# 03_Inputs_10-18.net
KiCad netlist of a schematic drawn in Altium Designer
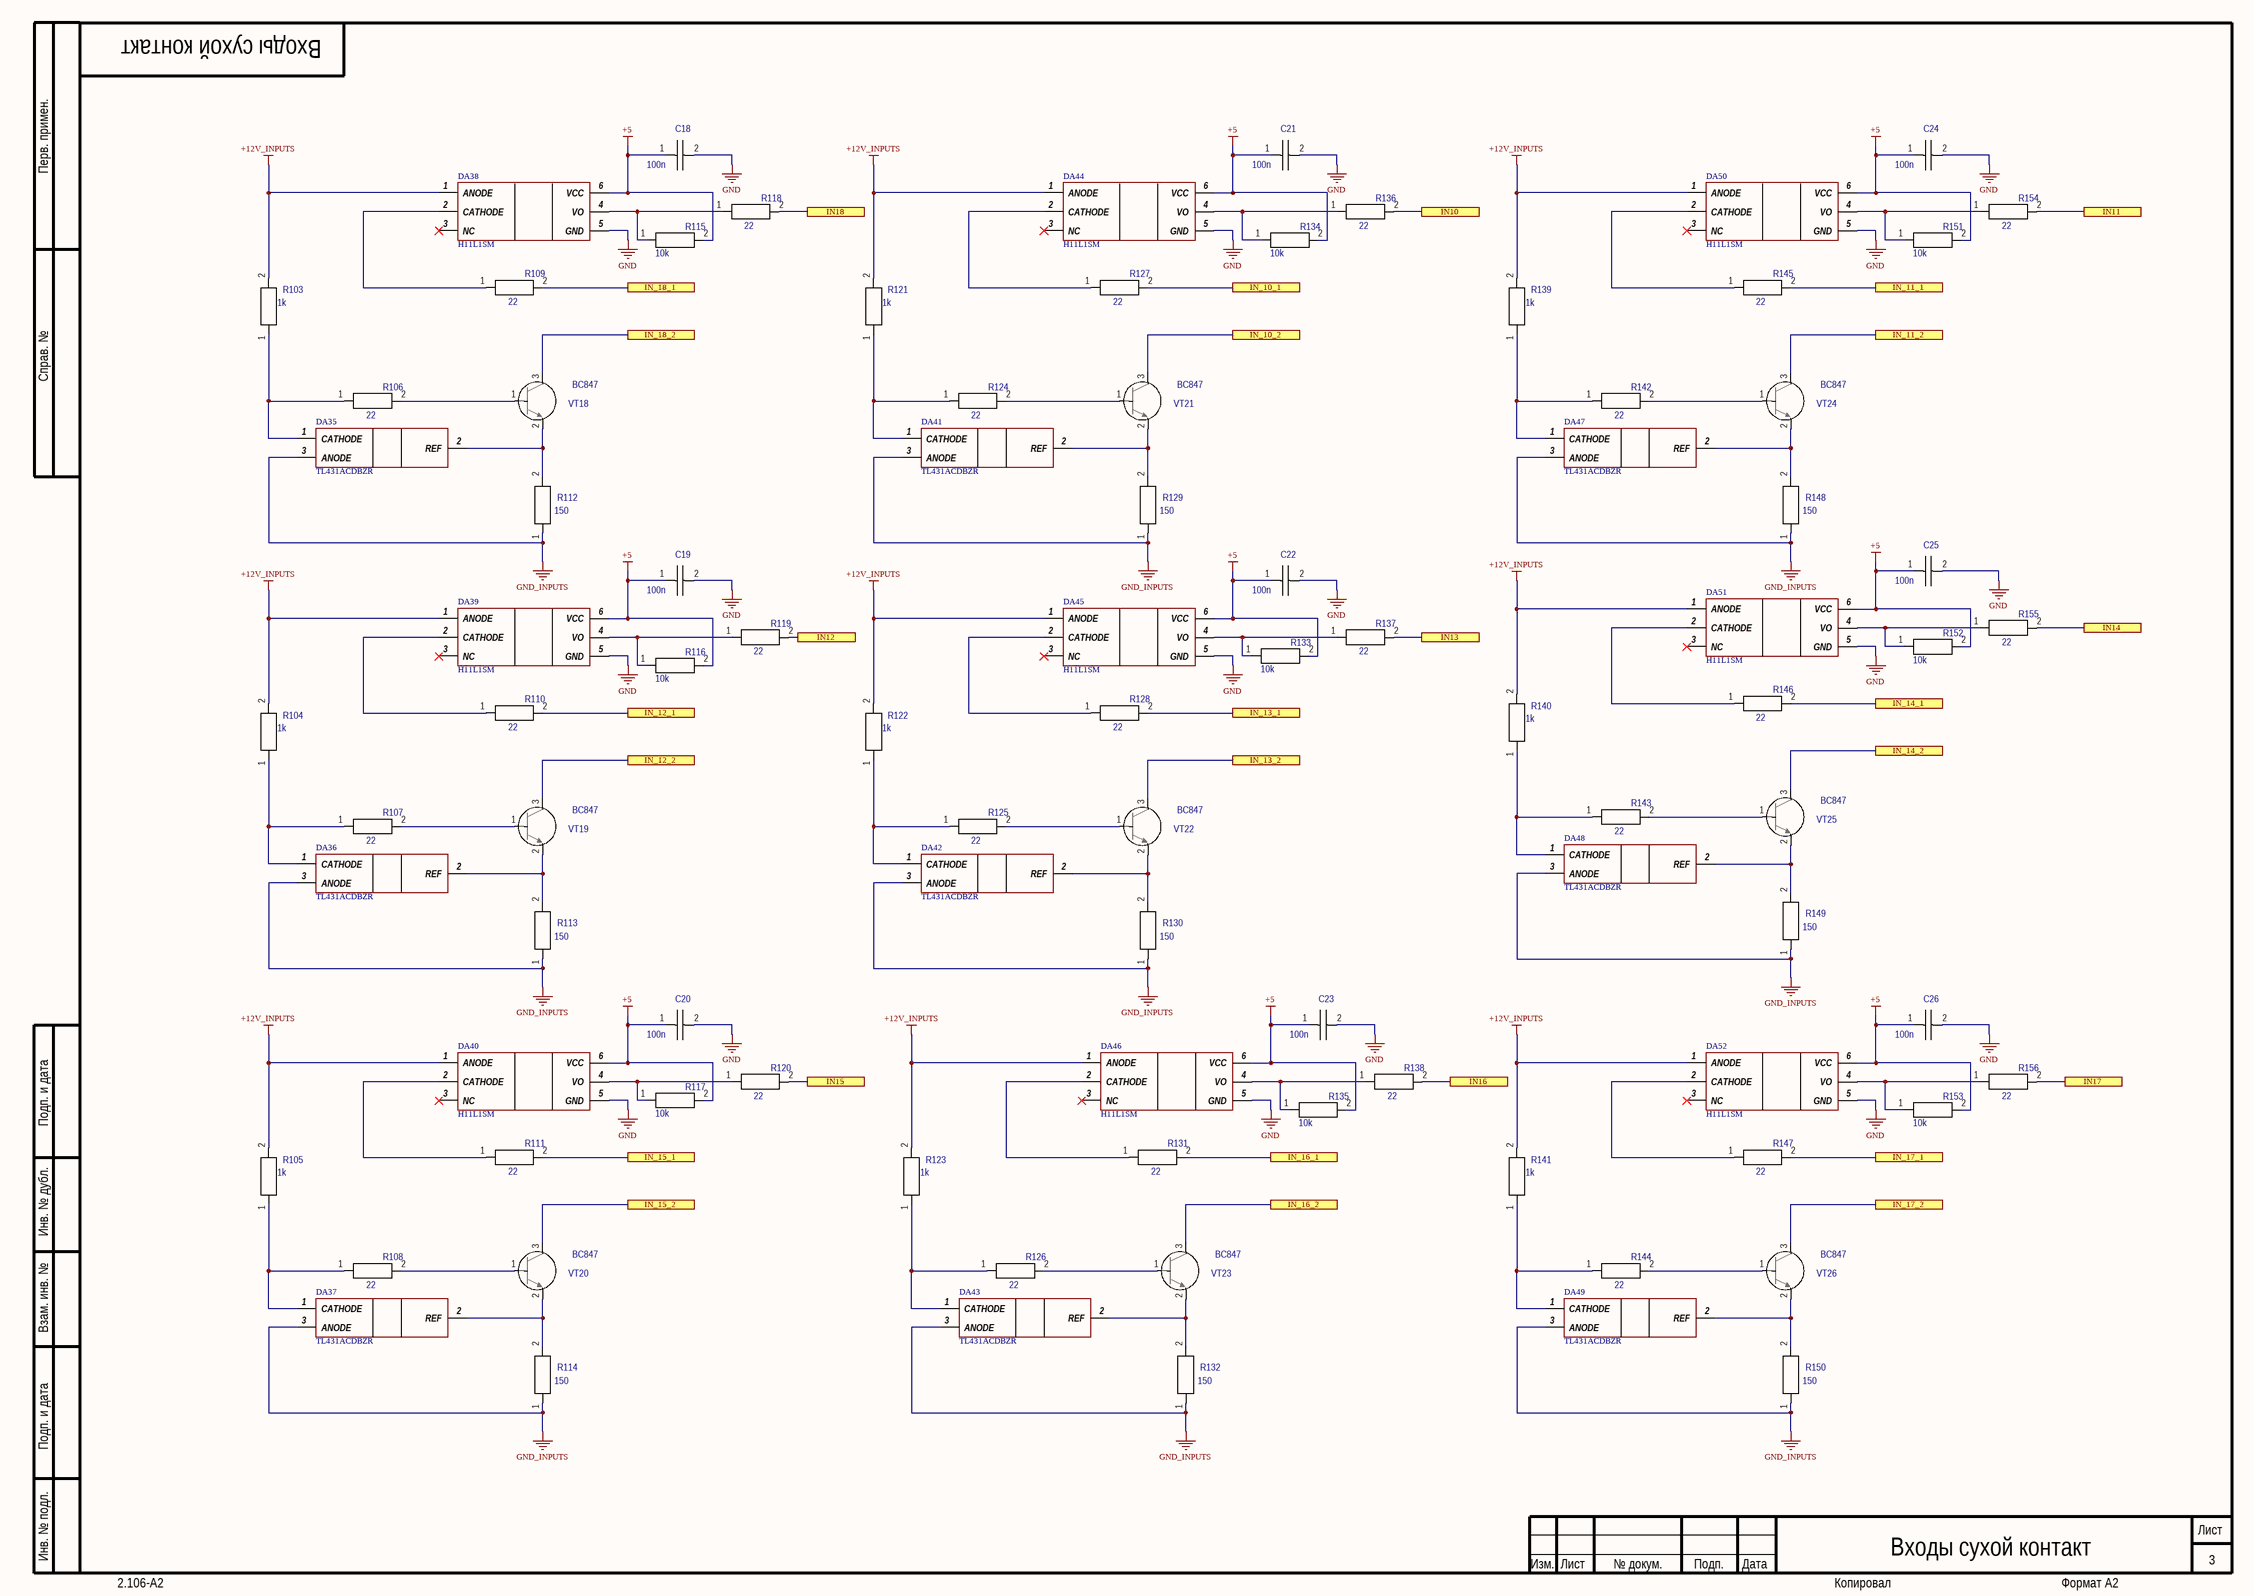
[diagram p0: 03_Inputs_10-18.SchDoc]

(export (version "E")
  (design (tool "Eeschema 10.0.6"))
  (components
    (comp (ref "C18")
      (value "100n")
      (footprint "C0603")
      (fields
        (field (name "PART NUMBER") "GRM188R71C104KA01D")
        (field (name "TOLERANCE") "±10%")
        (field (name "MANUFACTURER") "Murata Manufacturing")
      )
      (libsource (lib "AccessLibrary") (part "Capacitor"))
    )
    (comp (ref "C19")
      (value "100n")
      (footprint "C0603")
      (fields
        (field (name "PART NUMBER") "GRM188R71C104KA01D")
        (field (name "TOLERANCE") "±10%")
        (field (name "MANUFACTURER") "Murata Manufacturing")
      )
      (libsource (lib "AccessLibrary") (part "Capacitor"))
    )
    (comp (ref "C20")
      (value "100n")
      (footprint "C0603")
      (fields
        (field (name "PART NUMBER") "GRM188R71C104KA01D")
        (field (name "TOLERANCE") "±10%")
        (field (name "MANUFACTURER") "Murata Manufacturing")
      )
      (libsource (lib "AccessLibrary") (part "Capacitor"))
    )
    (comp (ref "C21")
      (value "100n")
      (footprint "C0603")
      (fields
        (field (name "PART NUMBER") "GRM188R71C104KA01D")
        (field (name "TOLERANCE") "±10%")
        (field (name "MANUFACTURER") "Murata Manufacturing")
      )
      (libsource (lib "AccessLibrary") (part "Capacitor"))
    )
    (comp (ref "C22")
      (value "100n")
      (footprint "C0603")
      (fields
        (field (name "PART NUMBER") "GRM188R71C104KA01D")
        (field (name "TOLERANCE") "±10%")
        (field (name "MANUFACTURER") "Murata Manufacturing")
      )
      (libsource (lib "AccessLibrary") (part "Capacitor"))
    )
    (comp (ref "C23")
      (value "100n")
      (footprint "C0603")
      (fields
        (field (name "PART NUMBER") "GRM188R71C104KA01D")
        (field (name "TOLERANCE") "±10%")
        (field (name "MANUFACTURER") "Murata Manufacturing")
      )
      (libsource (lib "AccessLibrary") (part "Capacitor"))
    )
    (comp (ref "C24")
      (value "100n")
      (footprint "C0603")
      (fields
        (field (name "PART NUMBER") "GRM188R71C104KA01D")
        (field (name "TOLERANCE") "±10%")
        (field (name "MANUFACTURER") "Murata Manufacturing")
      )
      (libsource (lib "AccessLibrary") (part "Capacitor"))
    )
    (comp (ref "C25")
      (value "100n")
      (footprint "C0603")
      (fields
        (field (name "PART NUMBER") "GRM188R71C104KA01D")
        (field (name "TOLERANCE") "±10%")
        (field (name "MANUFACTURER") "Murata Manufacturing")
      )
      (libsource (lib "AccessLibrary") (part "Capacitor"))
    )
    (comp (ref "C26")
      (value "100n")
      (footprint "C0603")
      (fields
        (field (name "PART NUMBER") "GRM188R71C104KA01D")
        (field (name "TOLERANCE") "±10%")
        (field (name "MANUFACTURER") "Murata Manufacturing")
      )
      (libsource (lib "AccessLibrary") (part "Capacitor"))
    )
    (comp (ref "DA35")
      (value "TL431ACDBZR")
      (footprint "board:SOT95P237X112-3N")
      (description "Integrated Circuit")
      (fields (field (name "MOUSER PART NUMBER") "595-TL431ACDBZR"))
      (libsource (lib "board") (part "TL431ACDBZR"))
    )
    (comp (ref "DA36")
      (value "TL431ACDBZR")
      (footprint "board:SOT95P237X112-3N")
      (description "Integrated Circuit")
      (fields (field (name "MOUSER PART NUMBER") "595-TL431ACDBZR"))
      (libsource (lib "board") (part "TL431ACDBZR"))
    )
    (comp (ref "DA37")
      (value "TL431ACDBZR")
      (footprint "board:SOT95P237X112-3N")
      (description "Integrated Circuit")
      (fields (field (name "MOUSER PART NUMBER") "595-TL431ACDBZR"))
      (libsource (lib "board") (part "TL431ACDBZR"))
    )
    (comp (ref "DA38")
      (value "H11L1SM")
      (footprint "board:SOP254P1030X460-6N")
      (description "Integrated Circuit")
      (libsource (lib "board") (part "H11L1SM"))
    )
    (comp (ref "DA39")
      (value "H11L1SM")
      (footprint "board:SOP254P1030X460-6N")
      (description "Integrated Circuit")
      (libsource (lib "board") (part "H11L1SM"))
    )
    (comp (ref "DA40")
      (value "H11L1SM")
      (footprint "board:SOP254P1030X460-6N")
      (description "Integrated Circuit")
      (libsource (lib "board") (part "H11L1SM"))
    )
    (comp (ref "DA41")
      (value "TL431ACDBZR")
      (footprint "board:SOT95P237X112-3N")
      (description "Integrated Circuit")
      (fields (field (name "MOUSER PART NUMBER") "595-TL431ACDBZR"))
      (libsource (lib "board") (part "TL431ACDBZR"))
    )
    (comp (ref "DA42")
      (value "TL431ACDBZR")
      (footprint "board:SOT95P237X112-3N")
      (description "Integrated Circuit")
      (fields (field (name "MOUSER PART NUMBER") "595-TL431ACDBZR"))
      (libsource (lib "board") (part "TL431ACDBZR"))
    )
    (comp (ref "DA43")
      (value "TL431ACDBZR")
      (footprint "board:SOT95P237X112-3N")
      (description "Integrated Circuit")
      (fields (field (name "MOUSER PART NUMBER") "595-TL431ACDBZR"))
      (libsource (lib "board") (part "TL431ACDBZR"))
    )
    (comp (ref "DA44")
      (value "H11L1SM")
      (footprint "board:SOP254P1030X460-6N")
      (description "Integrated Circuit")
      (libsource (lib "board") (part "H11L1SM"))
    )
    (comp (ref "DA45")
      (value "H11L1SM")
      (footprint "board:SOP254P1030X460-6N")
      (description "Integrated Circuit")
      (libsource (lib "board") (part "H11L1SM"))
    )
    (comp (ref "DA46")
      (value "H11L1SM")
      (footprint "board:SOP254P1030X460-6N")
      (description "Integrated Circuit")
      (libsource (lib "board") (part "H11L1SM"))
    )
    (comp (ref "DA47")
      (value "TL431ACDBZR")
      (footprint "board:SOT95P237X112-3N")
      (description "Integrated Circuit")
      (fields (field (name "MOUSER PART NUMBER") "595-TL431ACDBZR"))
      (libsource (lib "board") (part "TL431ACDBZR"))
    )
    (comp (ref "DA48")
      (value "TL431ACDBZR")
      (footprint "board:SOT95P237X112-3N")
      (description "Integrated Circuit")
      (fields (field (name "MOUSER PART NUMBER") "595-TL431ACDBZR"))
      (libsource (lib "board") (part "TL431ACDBZR"))
    )
    (comp (ref "DA49")
      (value "TL431ACDBZR")
      (footprint "board:SOT95P237X112-3N")
      (description "Integrated Circuit")
      (fields (field (name "MOUSER PART NUMBER") "595-TL431ACDBZR"))
      (libsource (lib "board") (part "TL431ACDBZR"))
    )
    (comp (ref "DA50")
      (value "H11L1SM")
      (footprint "board:SOP254P1030X460-6N")
      (description "Integrated Circuit")
      (libsource (lib "board") (part "H11L1SM"))
    )
    (comp (ref "DA51")
      (value "H11L1SM")
      (footprint "board:SOP254P1030X460-6N")
      (description "Integrated Circuit")
      (libsource (lib "board") (part "H11L1SM"))
    )
    (comp (ref "DA52")
      (value "H11L1SM")
      (footprint "board:SOP254P1030X460-6N")
      (description "Integrated Circuit")
      (libsource (lib "board") (part "H11L1SM"))
    )
    (comp (ref "R103")
      (value "1k")
      (footprint "RESC1608N")
      (fields
        (field (name "PART NUMBER") "RC0603FK-071KL")
        (field (name "TOLERANCE") "±1%")
        (field (name "MANUFACTURER") "Тайвань")
      )
      (libsource (lib "AccessLibrary") (part "Resistor"))
    )
    (comp (ref "R104")
      (value "1k")
      (footprint "RESC1608N")
      (fields
        (field (name "PART NUMBER") "RC0603FK-071KL")
        (field (name "TOLERANCE") "±1%")
        (field (name "MANUFACTURER") "Тайвань")
      )
      (libsource (lib "AccessLibrary") (part "Resistor"))
    )
    (comp (ref "R105")
      (value "1k")
      (footprint "RESC1608N")
      (fields
        (field (name "PART NUMBER") "RC0603FK-071KL")
        (field (name "TOLERANCE") "±1%")
        (field (name "MANUFACTURER") "Тайвань")
      )
      (libsource (lib "AccessLibrary") (part "Resistor"))
    )
    (comp (ref "R106")
      (value "22")
      (footprint "RESC1608N")
      (fields
        (field (name "PART NUMBER") "RC0603FK-0722RL")
        (field (name "TOLERANCE") "±1%")
        (field (name "MANUFACTURER") "Тайвань")
      )
      (libsource (lib "AccessLibrary") (part "Resistor"))
    )
    (comp (ref "R107")
      (value "22")
      (footprint "RESC1608N")
      (fields
        (field (name "PART NUMBER") "RC0603FK-0722RL")
        (field (name "TOLERANCE") "±1%")
        (field (name "MANUFACTURER") "Тайвань")
      )
      (libsource (lib "AccessLibrary") (part "Resistor"))
    )
    (comp (ref "R108")
      (value "22")
      (footprint "RESC1608N")
      (fields
        (field (name "PART NUMBER") "RC0603FK-0722RL")
        (field (name "TOLERANCE") "±1%")
        (field (name "MANUFACTURER") "Тайвань")
      )
      (libsource (lib "AccessLibrary") (part "Resistor"))
    )
    (comp (ref "R109")
      (value "22")
      (footprint "RESC1608N")
      (fields
        (field (name "PART NUMBER") "RC0603FK-0722RL")
        (field (name "TOLERANCE") "±1%")
        (field (name "MANUFACTURER") "Тайвань")
      )
      (libsource (lib "AccessLibrary") (part "Resistor"))
    )
    (comp (ref "R110")
      (value "22")
      (footprint "RESC1608N")
      (fields
        (field (name "PART NUMBER") "RC0603FK-0722RL")
        (field (name "TOLERANCE") "±1%")
        (field (name "MANUFACTURER") "Тайвань")
      )
      (libsource (lib "AccessLibrary") (part "Resistor"))
    )
    (comp (ref "R111")
      (value "22")
      (footprint "RESC1608N")
      (fields
        (field (name "PART NUMBER") "RC0603FK-0722RL")
        (field (name "TOLERANCE") "±1%")
        (field (name "MANUFACTURER") "Тайвань")
      )
      (libsource (lib "AccessLibrary") (part "Resistor"))
    )
    (comp (ref "R112")
      (value "150")
      (footprint "RESC1608N")
      (fields
        (field (name "PART NUMBER") "RC0603FK-07150RL")
        (field (name "TOLERANCE") "±1%")
        (field (name "MANUFACTURER") "Тайвань")
      )
      (libsource (lib "AccessLibrary") (part "Resistor"))
    )
    (comp (ref "R113")
      (value "150")
      (footprint "RESC1608N")
      (fields
        (field (name "PART NUMBER") "RC0603FK-07150RL")
        (field (name "TOLERANCE") "±1%")
        (field (name "MANUFACTURER") "Тайвань")
      )
      (libsource (lib "AccessLibrary") (part "Resistor"))
    )
    (comp (ref "R114")
      (value "150")
      (footprint "RESC1608N")
      (fields
        (field (name "PART NUMBER") "RC0603FK-07150RL")
        (field (name "TOLERANCE") "±1%")
        (field (name "MANUFACTURER") "Тайвань")
      )
      (libsource (lib "AccessLibrary") (part "Resistor"))
    )
    (comp (ref "R115")
      (value "10k")
      (footprint "RESC1608N")
      (fields
        (field (name "PART NUMBER") "RC0603FR-0710KL")
        (field (name "TOLERANCE") "±1%")
        (field (name "MANUFACTURER") "Тайвань")
      )
      (libsource (lib "AccessLibrary") (part "Resistor"))
    )
    (comp (ref "R116")
      (value "10k")
      (footprint "RESC1608N")
      (fields
        (field (name "PART NUMBER") "RC0603FR-0710KL")
        (field (name "TOLERANCE") "±1%")
        (field (name "MANUFACTURER") "Тайвань")
      )
      (libsource (lib "AccessLibrary") (part "Resistor"))
    )
    (comp (ref "R117")
      (value "10k")
      (footprint "RESC1608N")
      (fields
        (field (name "PART NUMBER") "RC0603FR-0710KL")
        (field (name "TOLERANCE") "±1%")
        (field (name "MANUFACTURER") "Тайвань")
      )
      (libsource (lib "AccessLibrary") (part "Resistor"))
    )
    (comp (ref "R118")
      (value "22")
      (footprint "RESC1608N")
      (fields
        (field (name "PART NUMBER") "RC0603FK-0722RL")
        (field (name "TOLERANCE") "±1%")
        (field (name "MANUFACTURER") "Тайвань")
      )
      (libsource (lib "AccessLibrary") (part "Resistor"))
    )
    (comp (ref "R119")
      (value "22")
      (footprint "RESC1608N")
      (fields
        (field (name "PART NUMBER") "RC0603FK-0722RL")
        (field (name "TOLERANCE") "±1%")
        (field (name "MANUFACTURER") "Тайвань")
      )
      (libsource (lib "AccessLibrary") (part "Resistor"))
    )
    (comp (ref "R120")
      (value "22")
      (footprint "RESC1608N")
      (fields
        (field (name "PART NUMBER") "RC0603FK-0722RL")
        (field (name "TOLERANCE") "±1%")
        (field (name "MANUFACTURER") "Тайвань")
      )
      (libsource (lib "AccessLibrary") (part "Resistor"))
    )
    (comp (ref "R121")
      (value "1k")
      (footprint "RESC1608N")
      (fields
        (field (name "PART NUMBER") "RC0603FK-071KL")
        (field (name "TOLERANCE") "±1%")
        (field (name "MANUFACTURER") "Тайвань")
      )
      (libsource (lib "AccessLibrary") (part "Resistor"))
    )
    (comp (ref "R122")
      (value "1k")
      (footprint "RESC1608N")
      (fields
        (field (name "PART NUMBER") "RC0603FK-071KL")
        (field (name "TOLERANCE") "±1%")
        (field (name "MANUFACTURER") "Тайвань")
      )
      (libsource (lib "AccessLibrary") (part "Resistor"))
    )
    (comp (ref "R123")
      (value "1k")
      (footprint "RESC1608N")
      (fields
        (field (name "PART NUMBER") "RC0603FK-071KL")
        (field (name "TOLERANCE") "±1%")
        (field (name "MANUFACTURER") "Тайвань")
      )
      (libsource (lib "AccessLibrary") (part "Resistor"))
    )
    (comp (ref "R124")
      (value "22")
      (footprint "RESC1608N")
      (fields
        (field (name "PART NUMBER") "RC0603FK-0722RL")
        (field (name "TOLERANCE") "±1%")
        (field (name "MANUFACTURER") "Тайвань")
      )
      (libsource (lib "AccessLibrary") (part "Resistor"))
    )
    (comp (ref "R125")
      (value "22")
      (footprint "RESC1608N")
      (fields
        (field (name "PART NUMBER") "RC0603FK-0722RL")
        (field (name "TOLERANCE") "±1%")
        (field (name "MANUFACTURER") "Тайвань")
      )
      (libsource (lib "AccessLibrary") (part "Resistor"))
    )
    (comp (ref "R126")
      (value "22")
      (footprint "RESC1608N")
      (fields
        (field (name "PART NUMBER") "RC0603FK-0722RL")
        (field (name "TOLERANCE") "±1%")
        (field (name "MANUFACTURER") "Тайвань")
      )
      (libsource (lib "AccessLibrary") (part "Resistor"))
    )
    (comp (ref "R127")
      (value "22")
      (footprint "RESC1608N")
      (fields
        (field (name "PART NUMBER") "RC0603FK-0722RL")
        (field (name "TOLERANCE") "±1%")
        (field (name "MANUFACTURER") "Тайвань")
      )
      (libsource (lib "AccessLibrary") (part "Resistor"))
    )
    (comp (ref "R128")
      (value "22")
      (footprint "RESC1608N")
      (fields
        (field (name "PART NUMBER") "RC0603FK-0722RL")
        (field (name "TOLERANCE") "±1%")
        (field (name "MANUFACTURER") "Тайвань")
      )
      (libsource (lib "AccessLibrary") (part "Resistor"))
    )
    (comp (ref "R129")
      (value "150")
      (footprint "RESC1608N")
      (fields
        (field (name "PART NUMBER") "RC0603FK-07150RL")
        (field (name "TOLERANCE") "±1%")
        (field (name "MANUFACTURER") "Тайвань")
      )
      (libsource (lib "AccessLibrary") (part "Resistor"))
    )
    (comp (ref "R130")
      (value "150")
      (footprint "RESC1608N")
      (fields
        (field (name "PART NUMBER") "RC0603FK-07150RL")
        (field (name "TOLERANCE") "±1%")
        (field (name "MANUFACTURER") "Тайвань")
      )
      (libsource (lib "AccessLibrary") (part "Resistor"))
    )
    (comp (ref "R131")
      (value "22")
      (footprint "RESC1608N")
      (fields
        (field (name "PART NUMBER") "RC0603FK-0722RL")
        (field (name "TOLERANCE") "±1%")
        (field (name "MANUFACTURER") "Тайвань")
      )
      (libsource (lib "AccessLibrary") (part "Resistor"))
    )
    (comp (ref "R132")
      (value "150")
      (footprint "RESC1608N")
      (fields
        (field (name "PART NUMBER") "RC0603FK-07150RL")
        (field (name "TOLERANCE") "±1%")
        (field (name "MANUFACTURER") "Тайвань")
      )
      (libsource (lib "AccessLibrary") (part "Resistor"))
    )
    (comp (ref "R133")
      (value "10k")
      (footprint "RESC1608N")
      (fields
        (field (name "PART NUMBER") "RC0603FR-0710KL")
        (field (name "TOLERANCE") "±1%")
        (field (name "MANUFACTURER") "Тайвань")
      )
      (libsource (lib "AccessLibrary") (part "Resistor"))
    )
    (comp (ref "R134")
      (value "10k")
      (footprint "RESC1608N")
      (fields
        (field (name "PART NUMBER") "RC0603FR-0710KL")
        (field (name "TOLERANCE") "±1%")
        (field (name "MANUFACTURER") "Тайвань")
      )
      (libsource (lib "AccessLibrary") (part "Resistor"))
    )
    (comp (ref "R135")
      (value "10k")
      (footprint "RESC1608N")
      (fields
        (field (name "PART NUMBER") "RC0603FR-0710KL")
        (field (name "TOLERANCE") "±1%")
        (field (name "MANUFACTURER") "Тайвань")
      )
      (libsource (lib "AccessLibrary") (part "Resistor"))
    )
    (comp (ref "R136")
      (value "22")
      (footprint "RESC1608N")
      (fields
        (field (name "PART NUMBER") "RC0603FK-0722RL")
        (field (name "TOLERANCE") "±1%")
        (field (name "MANUFACTURER") "Тайвань")
      )
      (libsource (lib "AccessLibrary") (part "Resistor"))
    )
    (comp (ref "R137")
      (value "22")
      (footprint "RESC1608N")
      (fields
        (field (name "PART NUMBER") "RC0603FK-0722RL")
        (field (name "TOLERANCE") "±1%")
        (field (name "MANUFACTURER") "Тайвань")
      )
      (libsource (lib "AccessLibrary") (part "Resistor"))
    )
    (comp (ref "R138")
      (value "22")
      (footprint "RESC1608N")
      (fields
        (field (name "PART NUMBER") "RC0603FK-0722RL")
        (field (name "TOLERANCE") "±1%")
        (field (name "MANUFACTURER") "Тайвань")
      )
      (libsource (lib "AccessLibrary") (part "Resistor"))
    )
    (comp (ref "R139")
      (value "1k")
      (footprint "RESC1608N")
      (fields
        (field (name "PART NUMBER") "RC0603FK-071KL")
        (field (name "TOLERANCE") "±1%")
        (field (name "MANUFACTURER") "Тайвань")
      )
      (libsource (lib "AccessLibrary") (part "Resistor"))
    )
    (comp (ref "R140")
      (value "1k")
      (footprint "RESC1608N")
      (fields
        (field (name "PART NUMBER") "RC0603FK-071KL")
        (field (name "TOLERANCE") "±1%")
        (field (name "MANUFACTURER") "Тайвань")
      )
      (libsource (lib "AccessLibrary") (part "Resistor"))
    )
    (comp (ref "R141")
      (value "1k")
      (footprint "RESC1608N")
      (fields
        (field (name "PART NUMBER") "RC0603FK-071KL")
        (field (name "TOLERANCE") "±1%")
        (field (name "MANUFACTURER") "Тайвань")
      )
      (libsource (lib "AccessLibrary") (part "Resistor"))
    )
    (comp (ref "R142")
      (value "22")
      (footprint "RESC1608N")
      (fields
        (field (name "PART NUMBER") "RC0603FK-0722RL")
        (field (name "TOLERANCE") "±1%")
        (field (name "MANUFACTURER") "Тайвань")
      )
      (libsource (lib "AccessLibrary") (part "Resistor"))
    )
    (comp (ref "R143")
      (value "22")
      (footprint "RESC1608N")
      (fields
        (field (name "PART NUMBER") "RC0603FK-0722RL")
        (field (name "TOLERANCE") "±1%")
        (field (name "MANUFACTURER") "Тайвань")
      )
      (libsource (lib "AccessLibrary") (part "Resistor"))
    )
    (comp (ref "R144")
      (value "22")
      (footprint "RESC1608N")
      (fields
        (field (name "PART NUMBER") "RC0603FK-0722RL")
        (field (name "TOLERANCE") "±1%")
        (field (name "MANUFACTURER") "Тайвань")
      )
      (libsource (lib "AccessLibrary") (part "Resistor"))
    )
    (comp (ref "R145")
      (value "22")
      (footprint "RESC1608N")
      (fields
        (field (name "PART NUMBER") "RC0603FK-0722RL")
        (field (name "TOLERANCE") "±1%")
        (field (name "MANUFACTURER") "Тайвань")
      )
      (libsource (lib "AccessLibrary") (part "Resistor"))
    )
    (comp (ref "R146")
      (value "22")
      (footprint "RESC1608N")
      (fields
        (field (name "PART NUMBER") "RC0603FK-0722RL")
        (field (name "TOLERANCE") "±1%")
        (field (name "MANUFACTURER") "Тайвань")
      )
      (libsource (lib "AccessLibrary") (part "Resistor"))
    )
    (comp (ref "R147")
      (value "22")
      (footprint "RESC1608N")
      (fields
        (field (name "PART NUMBER") "RC0603FK-0722RL")
        (field (name "TOLERANCE") "±1%")
        (field (name "MANUFACTURER") "Тайвань")
      )
      (libsource (lib "AccessLibrary") (part "Resistor"))
    )
    (comp (ref "R148")
      (value "150")
      (footprint "RESC1608N")
      (fields
        (field (name "PART NUMBER") "RC0603FK-07150RL")
        (field (name "TOLERANCE") "±1%")
        (field (name "MANUFACTURER") "Тайвань")
      )
      (libsource (lib "AccessLibrary") (part "Resistor"))
    )
    (comp (ref "R149")
      (value "150")
      (footprint "RESC1608N")
      (fields
        (field (name "PART NUMBER") "RC0603FK-07150RL")
        (field (name "TOLERANCE") "±1%")
        (field (name "MANUFACTURER") "Тайвань")
      )
      (libsource (lib "AccessLibrary") (part "Resistor"))
    )
    (comp (ref "R150")
      (value "150")
      (footprint "RESC1608N")
      (fields
        (field (name "PART NUMBER") "RC0603FK-07150RL")
        (field (name "TOLERANCE") "±1%")
        (field (name "MANUFACTURER") "Тайвань")
      )
      (libsource (lib "AccessLibrary") (part "Resistor"))
    )
    (comp (ref "R151")
      (value "10k")
      (footprint "RESC1608N")
      (fields
        (field (name "PART NUMBER") "RC0603FR-0710KL")
        (field (name "TOLERANCE") "±1%")
        (field (name "MANUFACTURER") "Тайвань")
      )
      (libsource (lib "AccessLibrary") (part "Resistor"))
    )
    (comp (ref "R152")
      (value "10k")
      (footprint "RESC1608N")
      (fields
        (field (name "PART NUMBER") "RC0603FR-0710KL")
        (field (name "TOLERANCE") "±1%")
        (field (name "MANUFACTURER") "Тайвань")
      )
      (libsource (lib "AccessLibrary") (part "Resistor"))
    )
    (comp (ref "R153")
      (value "10k")
      (footprint "RESC1608N")
      (fields
        (field (name "PART NUMBER") "RC0603FR-0710KL")
        (field (name "TOLERANCE") "±1%")
        (field (name "MANUFACTURER") "Тайвань")
      )
      (libsource (lib "AccessLibrary") (part "Resistor"))
    )
    (comp (ref "R154")
      (value "22")
      (footprint "RESC1608N")
      (fields
        (field (name "PART NUMBER") "RC0603FK-0722RL")
        (field (name "TOLERANCE") "±1%")
        (field (name "MANUFACTURER") "Тайвань")
      )
      (libsource (lib "AccessLibrary") (part "Resistor"))
    )
    (comp (ref "R155")
      (value "22")
      (footprint "RESC1608N")
      (fields
        (field (name "PART NUMBER") "RC0603FK-0722RL")
        (field (name "TOLERANCE") "±1%")
        (field (name "MANUFACTURER") "Тайвань")
      )
      (libsource (lib "AccessLibrary") (part "Resistor"))
    )
    (comp (ref "R156")
      (value "22")
      (footprint "RESC1608N")
      (fields
        (field (name "PART NUMBER") "RC0603FK-0722RL")
        (field (name "TOLERANCE") "±1%")
        (field (name "MANUFACTURER") "Тайвань")
      )
      (libsource (lib "AccessLibrary") (part "Resistor"))
    )
    (comp (ref "VT18")
      (value "BC847")
      (footprint "SOT23-3N")
      (fields (field (name "COM") "BC847") (field (name "MANUFACTURER") "NXP Semiconductor"))
      (libsource (lib "AccessLibrary") (part "Transistor_npn_1b-2e-3c"))
    )
    (comp (ref "VT19")
      (value "BC847")
      (footprint "SOT23-3N")
      (fields (field (name "COM") "BC847") (field (name "MANUFACTURER") "NXP Semiconductor"))
      (libsource (lib "AccessLibrary") (part "Transistor_npn_1b-2e-3c"))
    )
    (comp (ref "VT20")
      (value "BC847")
      (footprint "SOT23-3N")
      (fields (field (name "COM") "BC847") (field (name "MANUFACTURER") "NXP Semiconductor"))
      (libsource (lib "AccessLibrary") (part "Transistor_npn_1b-2e-3c"))
    )
    (comp (ref "VT21")
      (value "BC847")
      (footprint "SOT23-3N")
      (fields (field (name "COM") "BC847") (field (name "MANUFACTURER") "NXP Semiconductor"))
      (libsource (lib "AccessLibrary") (part "Transistor_npn_1b-2e-3c"))
    )
    (comp (ref "VT22")
      (value "BC847")
      (footprint "SOT23-3N")
      (fields (field (name "COM") "BC847") (field (name "MANUFACTURER") "NXP Semiconductor"))
      (libsource (lib "AccessLibrary") (part "Transistor_npn_1b-2e-3c"))
    )
    (comp (ref "VT23")
      (value "BC847")
      (footprint "SOT23-3N")
      (fields (field (name "COM") "BC847") (field (name "MANUFACTURER") "NXP Semiconductor"))
      (libsource (lib "AccessLibrary") (part "Transistor_npn_1b-2e-3c"))
    )
    (comp (ref "VT24")
      (value "BC847")
      (footprint "SOT23-3N")
      (fields (field (name "COM") "BC847") (field (name "MANUFACTURER") "NXP Semiconductor"))
      (libsource (lib "AccessLibrary") (part "Transistor_npn_1b-2e-3c"))
    )
    (comp (ref "VT25")
      (value "BC847")
      (footprint "SOT23-3N")
      (fields (field (name "COM") "BC847") (field (name "MANUFACTURER") "NXP Semiconductor"))
      (libsource (lib "AccessLibrary") (part "Transistor_npn_1b-2e-3c"))
    )
    (comp (ref "VT26")
      (value "BC847")
      (footprint "SOT23-3N")
      (fields (field (name "COM") "BC847") (field (name "MANUFACTURER") "NXP Semiconductor"))
      (libsource (lib "AccessLibrary") (part "Transistor_npn_1b-2e-3c"))
    )
  )
  (nets
    (net (code "1") (name "+5") (class "Default")
      (node (ref "C18") (pin "1") (pinfunction "1_1") (pintype "passive"))
      (node (ref "C19") (pin "1") (pinfunction "1_1") (pintype "passive"))
      (node (ref "C20") (pin "1") (pinfunction "1_1") (pintype "passive"))
      (node (ref "C21") (pin "1") (pinfunction "1_1") (pintype "passive"))
      (node (ref "C22") (pin "1") (pinfunction "1_1") (pintype "passive"))
      (node (ref "C23") (pin "1") (pinfunction "1_1") (pintype "passive"))
      (node (ref "C24") (pin "1") (pinfunction "1_1") (pintype "passive"))
      (node (ref "C25") (pin "1") (pinfunction "1_1") (pintype "passive"))
      (node (ref "C26") (pin "1") (pinfunction "1_1") (pintype "passive"))
      (node (ref "DA38") (pin "6") (pinfunction "VCC_6") (pintype "passive"))
      (node (ref "DA39") (pin "6") (pinfunction "VCC_6") (pintype "passive"))
      (node (ref "DA40") (pin "6") (pinfunction "VCC_6") (pintype "passive"))
      (node (ref "DA44") (pin "6") (pinfunction "VCC_6") (pintype "passive"))
      (node (ref "DA45") (pin "6") (pinfunction "VCC_6") (pintype "passive"))
      (node (ref "DA46") (pin "6") (pinfunction "VCC_6") (pintype "passive"))
      (node (ref "DA50") (pin "6") (pinfunction "VCC_6") (pintype "passive"))
      (node (ref "DA51") (pin "6") (pinfunction "VCC_6") (pintype "passive"))
      (node (ref "DA52") (pin "6") (pinfunction "VCC_6") (pintype "passive"))
      (node (ref "R115") (pin "2") (pinfunction "2_2") (pintype "passive"))
      (node (ref "R116") (pin "2") (pinfunction "2_2") (pintype "passive"))
      (node (ref "R117") (pin "2") (pinfunction "2_2") (pintype "passive"))
      (node (ref "R133") (pin "2") (pinfunction "2_2") (pintype "passive"))
      (node (ref "R134") (pin "2") (pinfunction "2_2") (pintype "passive"))
      (node (ref "R135") (pin "2") (pinfunction "2_2") (pintype "passive"))
      (node (ref "R151") (pin "2") (pinfunction "2_2") (pintype "passive"))
      (node (ref "R152") (pin "2") (pinfunction "2_2") (pintype "passive"))
      (node (ref "R153") (pin "2") (pinfunction "2_2") (pintype "passive"))
    )
    (net (code "2") (name "+12V_INPUTS") (class "Default")
      (node (ref "DA38") (pin "1") (pinfunction "ANODE_1") (pintype "passive"))
      (node (ref "DA39") (pin "1") (pinfunction "ANODE_1") (pintype "passive"))
      (node (ref "DA40") (pin "1") (pinfunction "ANODE_1") (pintype "passive"))
      (node (ref "DA44") (pin "1") (pinfunction "ANODE_1") (pintype "passive"))
      (node (ref "DA45") (pin "1") (pinfunction "ANODE_1") (pintype "passive"))
      (node (ref "DA46") (pin "1") (pinfunction "ANODE_1") (pintype "passive"))
      (node (ref "DA50") (pin "1") (pinfunction "ANODE_1") (pintype "passive"))
      (node (ref "DA51") (pin "1") (pinfunction "ANODE_1") (pintype "passive"))
      (node (ref "DA52") (pin "1") (pinfunction "ANODE_1") (pintype "passive"))
      (node (ref "R103") (pin "2") (pinfunction "2_2") (pintype "passive"))
      (node (ref "R104") (pin "2") (pinfunction "2_2") (pintype "passive"))
      (node (ref "R105") (pin "2") (pinfunction "2_2") (pintype "passive"))
      (node (ref "R121") (pin "2") (pinfunction "2_2") (pintype "passive"))
      (node (ref "R122") (pin "2") (pinfunction "2_2") (pintype "passive"))
      (node (ref "R123") (pin "2") (pinfunction "2_2") (pintype "passive"))
      (node (ref "R139") (pin "2") (pinfunction "2_2") (pintype "passive"))
      (node (ref "R140") (pin "2") (pinfunction "2_2") (pintype "passive"))
      (node (ref "R141") (pin "2") (pinfunction "2_2") (pintype "passive"))
    )
    (net (code "3") (name "/IN10") (class "Default")
      (node (ref "R136") (pin "2") (pinfunction "2_2") (pintype "passive"))
    )
    (net (code "4") (name "/IN11") (class "Default")
      (node (ref "R154") (pin "2") (pinfunction "2_2") (pintype "passive"))
    )
    (net (code "5") (name "/IN12") (class "Default")
      (node (ref "R119") (pin "2") (pinfunction "2_2") (pintype "passive"))
    )
    (net (code "6") (name "/IN13") (class "Default")
      (node (ref "R137") (pin "2") (pinfunction "2_2") (pintype "passive"))
    )
    (net (code "7") (name "/IN14") (class "Default")
      (node (ref "R155") (pin "2") (pinfunction "2_2") (pintype "passive"))
    )
    (net (code "8") (name "/IN15") (class "Default")
      (node (ref "R120") (pin "2") (pinfunction "2_2") (pintype "passive"))
    )
    (net (code "9") (name "/IN16") (class "Default")
      (node (ref "R138") (pin "2") (pinfunction "2_2") (pintype "passive"))
    )
    (net (code "10") (name "/IN17") (class "Default")
      (node (ref "R156") (pin "2") (pinfunction "2_2") (pintype "passive"))
    )
    (net (code "11") (name "/IN18") (class "Default")
      (node (ref "R118") (pin "2") (pinfunction "2_2") (pintype "passive"))
    )
    (net (code "12") (name "/IN_10_1") (class "Default")
      (node (ref "R127") (pin "2") (pinfunction "2_2") (pintype "passive"))
    )
    (net (code "13") (name "/IN_10_2") (class "Default")
      (node (ref "VT21") (pin "3") (pinfunction "3_3") (pintype "passive"))
    )
    (net (code "14") (name "/IN_11_1") (class "Default")
      (node (ref "R145") (pin "2") (pinfunction "2_2") (pintype "passive"))
    )
    (net (code "15") (name "/IN_11_2") (class "Default")
      (node (ref "VT24") (pin "3") (pinfunction "3_3") (pintype "passive"))
    )
    (net (code "16") (name "/IN_12_1") (class "Default")
      (node (ref "R110") (pin "2") (pinfunction "2_2") (pintype "passive"))
    )
    (net (code "17") (name "/IN_12_2") (class "Default")
      (node (ref "VT19") (pin "3") (pinfunction "3_3") (pintype "passive"))
    )
    (net (code "18") (name "/IN_13_1") (class "Default")
      (node (ref "R128") (pin "2") (pinfunction "2_2") (pintype "passive"))
    )
    (net (code "19") (name "/IN_13_2") (class "Default")
      (node (ref "VT22") (pin "3") (pinfunction "3_3") (pintype "passive"))
    )
    (net (code "20") (name "/IN_14_1") (class "Default")
      (node (ref "R146") (pin "2") (pinfunction "2_2") (pintype "passive"))
    )
    (net (code "21") (name "/IN_14_2") (class "Default")
      (node (ref "VT25") (pin "3") (pinfunction "3_3") (pintype "passive"))
    )
    (net (code "22") (name "/IN_15_1") (class "Default")
      (node (ref "R111") (pin "2") (pinfunction "2_2") (pintype "passive"))
    )
    (net (code "23") (name "/IN_15_2") (class "Default")
      (node (ref "VT20") (pin "3") (pinfunction "3_3") (pintype "passive"))
    )
    (net (code "24") (name "/IN_16_1") (class "Default")
      (node (ref "R131") (pin "2") (pinfunction "2_2") (pintype "passive"))
    )
    (net (code "25") (name "/IN_16_2") (class "Default")
      (node (ref "VT23") (pin "3") (pinfunction "3_3") (pintype "passive"))
    )
    (net (code "26") (name "/IN_17_1") (class "Default")
      (node (ref "R147") (pin "2") (pinfunction "2_2") (pintype "passive"))
    )
    (net (code "27") (name "/IN_17_2") (class "Default")
      (node (ref "VT26") (pin "3") (pinfunction "3_3") (pintype "passive"))
    )
    (net (code "28") (name "/IN_18_1") (class "Default")
      (node (ref "R109") (pin "2") (pinfunction "2_2") (pintype "passive"))
    )
    (net (code "29") (name "/IN_18_2") (class "Default")
      (node (ref "VT18") (pin "3") (pinfunction "3_3") (pintype "passive"))
    )
    (net (code "30") (name "GND") (class "Default")
      (node (ref "C18") (pin "2") (pinfunction "2_2") (pintype "passive"))
      (node (ref "C19") (pin "2") (pinfunction "2_2") (pintype "passive"))
      (node (ref "C20") (pin "2") (pinfunction "2_2") (pintype "passive"))
      (node (ref "C21") (pin "2") (pinfunction "2_2") (pintype "passive"))
      (node (ref "C22") (pin "2") (pinfunction "2_2") (pintype "passive"))
      (node (ref "C23") (pin "2") (pinfunction "2_2") (pintype "passive"))
      (node (ref "C24") (pin "2") (pinfunction "2_2") (pintype "passive"))
      (node (ref "C25") (pin "2") (pinfunction "2_2") (pintype "passive"))
      (node (ref "C26") (pin "2") (pinfunction "2_2") (pintype "passive"))
      (node (ref "DA38") (pin "5") (pinfunction "GND_5") (pintype "passive"))
      (node (ref "DA39") (pin "5") (pinfunction "GND_5") (pintype "passive"))
      (node (ref "DA40") (pin "5") (pinfunction "GND_5") (pintype "passive"))
      (node (ref "DA44") (pin "5") (pinfunction "GND_5") (pintype "passive"))
      (node (ref "DA45") (pin "5") (pinfunction "GND_5") (pintype "passive"))
      (node (ref "DA46") (pin "5") (pinfunction "GND_5") (pintype "passive"))
      (node (ref "DA50") (pin "5") (pinfunction "GND_5") (pintype "passive"))
      (node (ref "DA51") (pin "5") (pinfunction "GND_5") (pintype "passive"))
      (node (ref "DA52") (pin "5") (pinfunction "GND_5") (pintype "passive"))
    )
    (net (code "31") (name "GND_INPUTS") (class "Default")
      (node (ref "DA35") (pin "3") (pinfunction "ANODE_3") (pintype "passive"))
      (node (ref "DA36") (pin "3") (pinfunction "ANODE_3") (pintype "passive"))
      (node (ref "DA37") (pin "3") (pinfunction "ANODE_3") (pintype "passive"))
      (node (ref "DA41") (pin "3") (pinfunction "ANODE_3") (pintype "passive"))
      (node (ref "DA42") (pin "3") (pinfunction "ANODE_3") (pintype "passive"))
      (node (ref "DA43") (pin "3") (pinfunction "ANODE_3") (pintype "passive"))
      (node (ref "DA47") (pin "3") (pinfunction "ANODE_3") (pintype "passive"))
      (node (ref "DA48") (pin "3") (pinfunction "ANODE_3") (pintype "passive"))
      (node (ref "DA49") (pin "3") (pinfunction "ANODE_3") (pintype "passive"))
      (node (ref "R112") (pin "1") (pinfunction "1_1") (pintype "passive"))
      (node (ref "R113") (pin "1") (pinfunction "1_1") (pintype "passive"))
      (node (ref "R114") (pin "1") (pinfunction "1_1") (pintype "passive"))
      (node (ref "R129") (pin "1") (pinfunction "1_1") (pintype "passive"))
      (node (ref "R130") (pin "1") (pinfunction "1_1") (pintype "passive"))
      (node (ref "R132") (pin "1") (pinfunction "1_1") (pintype "passive"))
      (node (ref "R148") (pin "1") (pinfunction "1_1") (pintype "passive"))
      (node (ref "R149") (pin "1") (pinfunction "1_1") (pintype "passive"))
      (node (ref "R150") (pin "1") (pinfunction "1_1") (pintype "passive"))
    )
    (net (code "32") (name "Net-(DA35-CATHODE)") (class "Default")
      (node (ref "DA35") (pin "1") (pinfunction "CATHODE_1") (pintype "passive"))
      (node (ref "R103") (pin "1") (pinfunction "1_1") (pintype "passive"))
      (node (ref "R106") (pin "1") (pinfunction "1_1") (pintype "passive"))
    )
    (net (code "33") (name "Net-(DA35-REF)") (class "Default")
      (node (ref "DA35") (pin "2") (pinfunction "REF_2") (pintype "passive"))
      (node (ref "R112") (pin "2") (pinfunction "2_2") (pintype "passive"))
      (node (ref "VT18") (pin "2") (pinfunction "2_2") (pintype "passive"))
    )
    (net (code "34") (name "Net-(DA36-CATHODE)") (class "Default")
      (node (ref "DA36") (pin "1") (pinfunction "CATHODE_1") (pintype "passive"))
      (node (ref "R104") (pin "1") (pinfunction "1_1") (pintype "passive"))
      (node (ref "R107") (pin "1") (pinfunction "1_1") (pintype "passive"))
    )
    (net (code "35") (name "Net-(DA36-REF)") (class "Default")
      (node (ref "DA36") (pin "2") (pinfunction "REF_2") (pintype "passive"))
      (node (ref "R113") (pin "2") (pinfunction "2_2") (pintype "passive"))
      (node (ref "VT19") (pin "2") (pinfunction "2_2") (pintype "passive"))
    )
    (net (code "36") (name "Net-(DA37-CATHODE)") (class "Default")
      (node (ref "DA37") (pin "1") (pinfunction "CATHODE_1") (pintype "passive"))
      (node (ref "R105") (pin "1") (pinfunction "1_1") (pintype "passive"))
      (node (ref "R108") (pin "1") (pinfunction "1_1") (pintype "passive"))
    )
    (net (code "37") (name "Net-(DA37-REF)") (class "Default")
      (node (ref "DA37") (pin "2") (pinfunction "REF_2") (pintype "passive"))
      (node (ref "R114") (pin "2") (pinfunction "2_2") (pintype "passive"))
      (node (ref "VT20") (pin "2") (pinfunction "2_2") (pintype "passive"))
    )
    (net (code "38") (name "Net-(DA38-CATHODE)") (class "Default")
      (node (ref "DA38") (pin "2") (pinfunction "CATHODE_2") (pintype "passive"))
      (node (ref "R109") (pin "1") (pinfunction "1_1") (pintype "passive"))
    )
    (net (code "39") (name "Net-(DA38-VO)") (class "Default")
      (node (ref "DA38") (pin "4") (pinfunction "VO_4") (pintype "passive"))
      (node (ref "R115") (pin "1") (pinfunction "1_1") (pintype "passive"))
      (node (ref "R118") (pin "1") (pinfunction "1_1") (pintype "passive"))
    )
    (net (code "40") (name "Net-(DA39-CATHODE)") (class "Default")
      (node (ref "DA39") (pin "2") (pinfunction "CATHODE_2") (pintype "passive"))
      (node (ref "R110") (pin "1") (pinfunction "1_1") (pintype "passive"))
    )
    (net (code "41") (name "Net-(DA39-VO)") (class "Default")
      (node (ref "DA39") (pin "4") (pinfunction "VO_4") (pintype "passive"))
      (node (ref "R116") (pin "1") (pinfunction "1_1") (pintype "passive"))
      (node (ref "R119") (pin "1") (pinfunction "1_1") (pintype "passive"))
    )
    (net (code "42") (name "Net-(DA40-CATHODE)") (class "Default")
      (node (ref "DA40") (pin "2") (pinfunction "CATHODE_2") (pintype "passive"))
      (node (ref "R111") (pin "1") (pinfunction "1_1") (pintype "passive"))
    )
    (net (code "43") (name "Net-(DA40-VO)") (class "Default")
      (node (ref "DA40") (pin "4") (pinfunction "VO_4") (pintype "passive"))
      (node (ref "R117") (pin "1") (pinfunction "1_1") (pintype "passive"))
      (node (ref "R120") (pin "1") (pinfunction "1_1") (pintype "passive"))
    )
    (net (code "44") (name "Net-(DA41-CATHODE)") (class "Default")
      (node (ref "DA41") (pin "1") (pinfunction "CATHODE_1") (pintype "passive"))
      (node (ref "R121") (pin "1") (pinfunction "1_1") (pintype "passive"))
      (node (ref "R124") (pin "1") (pinfunction "1_1") (pintype "passive"))
    )
    (net (code "45") (name "Net-(DA41-REF)") (class "Default")
      (node (ref "DA41") (pin "2") (pinfunction "REF_2") (pintype "passive"))
      (node (ref "R129") (pin "2") (pinfunction "2_2") (pintype "passive"))
      (node (ref "VT21") (pin "2") (pinfunction "2_2") (pintype "passive"))
    )
    (net (code "46") (name "Net-(DA42-CATHODE)") (class "Default")
      (node (ref "DA42") (pin "1") (pinfunction "CATHODE_1") (pintype "passive"))
      (node (ref "R122") (pin "1") (pinfunction "1_1") (pintype "passive"))
      (node (ref "R125") (pin "1") (pinfunction "1_1") (pintype "passive"))
    )
    (net (code "47") (name "Net-(DA42-REF)") (class "Default")
      (node (ref "DA42") (pin "2") (pinfunction "REF_2") (pintype "passive"))
      (node (ref "R130") (pin "2") (pinfunction "2_2") (pintype "passive"))
      (node (ref "VT22") (pin "2") (pinfunction "2_2") (pintype "passive"))
    )
    (net (code "48") (name "Net-(DA43-CATHODE)") (class "Default")
      (node (ref "DA43") (pin "1") (pinfunction "CATHODE_1") (pintype "passive"))
      (node (ref "R123") (pin "1") (pinfunction "1_1") (pintype "passive"))
      (node (ref "R126") (pin "1") (pinfunction "1_1") (pintype "passive"))
    )
    (net (code "49") (name "Net-(DA43-REF)") (class "Default")
      (node (ref "DA43") (pin "2") (pinfunction "REF_2") (pintype "passive"))
      (node (ref "R132") (pin "2") (pinfunction "2_2") (pintype "passive"))
      (node (ref "VT23") (pin "2") (pinfunction "2_2") (pintype "passive"))
    )
    (net (code "50") (name "Net-(DA44-CATHODE)") (class "Default")
      (node (ref "DA44") (pin "2") (pinfunction "CATHODE_2") (pintype "passive"))
      (node (ref "R127") (pin "1") (pinfunction "1_1") (pintype "passive"))
    )
    (net (code "51") (name "Net-(DA44-VO)") (class "Default")
      (node (ref "DA44") (pin "4") (pinfunction "VO_4") (pintype "passive"))
      (node (ref "R134") (pin "1") (pinfunction "1_1") (pintype "passive"))
      (node (ref "R136") (pin "1") (pinfunction "1_1") (pintype "passive"))
    )
    (net (code "52") (name "Net-(DA45-CATHODE)") (class "Default")
      (node (ref "DA45") (pin "2") (pinfunction "CATHODE_2") (pintype "passive"))
      (node (ref "R128") (pin "1") (pinfunction "1_1") (pintype "passive"))
    )
    (net (code "53") (name "Net-(DA45-VO)") (class "Default")
      (node (ref "DA45") (pin "4") (pinfunction "VO_4") (pintype "passive"))
      (node (ref "R133") (pin "1") (pinfunction "1_1") (pintype "passive"))
      (node (ref "R137") (pin "1") (pinfunction "1_1") (pintype "passive"))
    )
    (net (code "54") (name "Net-(DA46-CATHODE)") (class "Default")
      (node (ref "DA46") (pin "2") (pinfunction "CATHODE_2") (pintype "passive"))
      (node (ref "R131") (pin "1") (pinfunction "1_1") (pintype "passive"))
    )
    (net (code "55") (name "Net-(DA46-VO)") (class "Default")
      (node (ref "DA46") (pin "4") (pinfunction "VO_4") (pintype "passive"))
      (node (ref "R135") (pin "1") (pinfunction "1_1") (pintype "passive"))
      (node (ref "R138") (pin "1") (pinfunction "1_1") (pintype "passive"))
    )
    (net (code "56") (name "Net-(DA47-CATHODE)") (class "Default")
      (node (ref "DA47") (pin "1") (pinfunction "CATHODE_1") (pintype "passive"))
      (node (ref "R139") (pin "1") (pinfunction "1_1") (pintype "passive"))
      (node (ref "R142") (pin "1") (pinfunction "1_1") (pintype "passive"))
    )
    (net (code "57") (name "Net-(DA47-REF)") (class "Default")
      (node (ref "DA47") (pin "2") (pinfunction "REF_2") (pintype "passive"))
      (node (ref "R148") (pin "2") (pinfunction "2_2") (pintype "passive"))
      (node (ref "VT24") (pin "2") (pinfunction "2_2") (pintype "passive"))
    )
    (net (code "58") (name "Net-(DA48-CATHODE)") (class "Default")
      (node (ref "DA48") (pin "1") (pinfunction "CATHODE_1") (pintype "passive"))
      (node (ref "R140") (pin "1") (pinfunction "1_1") (pintype "passive"))
      (node (ref "R143") (pin "1") (pinfunction "1_1") (pintype "passive"))
    )
    (net (code "59") (name "Net-(DA48-REF)") (class "Default")
      (node (ref "DA48") (pin "2") (pinfunction "REF_2") (pintype "passive"))
      (node (ref "R149") (pin "2") (pinfunction "2_2") (pintype "passive"))
      (node (ref "VT25") (pin "2") (pinfunction "2_2") (pintype "passive"))
    )
    (net (code "60") (name "Net-(DA49-CATHODE)") (class "Default")
      (node (ref "DA49") (pin "1") (pinfunction "CATHODE_1") (pintype "passive"))
      (node (ref "R141") (pin "1") (pinfunction "1_1") (pintype "passive"))
      (node (ref "R144") (pin "1") (pinfunction "1_1") (pintype "passive"))
    )
    (net (code "61") (name "Net-(DA49-REF)") (class "Default")
      (node (ref "DA49") (pin "2") (pinfunction "REF_2") (pintype "passive"))
      (node (ref "R150") (pin "2") (pinfunction "2_2") (pintype "passive"))
      (node (ref "VT26") (pin "2") (pinfunction "2_2") (pintype "passive"))
    )
    (net (code "62") (name "Net-(DA50-CATHODE)") (class "Default")
      (node (ref "DA50") (pin "2") (pinfunction "CATHODE_2") (pintype "passive"))
      (node (ref "R145") (pin "1") (pinfunction "1_1") (pintype "passive"))
    )
    (net (code "63") (name "Net-(DA50-VO)") (class "Default")
      (node (ref "DA50") (pin "4") (pinfunction "VO_4") (pintype "passive"))
      (node (ref "R151") (pin "1") (pinfunction "1_1") (pintype "passive"))
      (node (ref "R154") (pin "1") (pinfunction "1_1") (pintype "passive"))
    )
    (net (code "64") (name "Net-(DA51-CATHODE)") (class "Default")
      (node (ref "DA51") (pin "2") (pinfunction "CATHODE_2") (pintype "passive"))
      (node (ref "R146") (pin "1") (pinfunction "1_1") (pintype "passive"))
    )
    (net (code "65") (name "Net-(DA51-VO)") (class "Default")
      (node (ref "DA51") (pin "4") (pinfunction "VO_4") (pintype "passive"))
      (node (ref "R152") (pin "1") (pinfunction "1_1") (pintype "passive"))
      (node (ref "R155") (pin "1") (pinfunction "1_1") (pintype "passive"))
    )
    (net (code "66") (name "Net-(DA52-CATHODE)") (class "Default")
      (node (ref "DA52") (pin "2") (pinfunction "CATHODE_2") (pintype "passive"))
      (node (ref "R147") (pin "1") (pinfunction "1_1") (pintype "passive"))
    )
    (net (code "67") (name "Net-(DA52-VO)") (class "Default")
      (node (ref "DA52") (pin "4") (pinfunction "VO_4") (pintype "passive"))
      (node (ref "R153") (pin "1") (pinfunction "1_1") (pintype "passive"))
      (node (ref "R156") (pin "1") (pinfunction "1_1") (pintype "passive"))
    )
    (net (code "68") (name "Net-(R106-Pad2)") (class "Default")
      (node (ref "R106") (pin "2") (pinfunction "2_2") (pintype "passive"))
      (node (ref "VT18") (pin "1") (pinfunction "1_1") (pintype "passive"))
    )
    (net (code "69") (name "Net-(R107-Pad2)") (class "Default")
      (node (ref "R107") (pin "2") (pinfunction "2_2") (pintype "passive"))
      (node (ref "VT19") (pin "1") (pinfunction "1_1") (pintype "passive"))
    )
    (net (code "70") (name "Net-(R108-Pad2)") (class "Default")
      (node (ref "R108") (pin "2") (pinfunction "2_2") (pintype "passive"))
      (node (ref "VT20") (pin "1") (pinfunction "1_1") (pintype "passive"))
    )
    (net (code "71") (name "Net-(R124-Pad2)") (class "Default")
      (node (ref "R124") (pin "2") (pinfunction "2_2") (pintype "passive"))
      (node (ref "VT21") (pin "1") (pinfunction "1_1") (pintype "passive"))
    )
    (net (code "72") (name "Net-(R125-Pad2)") (class "Default")
      (node (ref "R125") (pin "2") (pinfunction "2_2") (pintype "passive"))
      (node (ref "VT22") (pin "1") (pinfunction "1_1") (pintype "passive"))
    )
    (net (code "73") (name "Net-(R126-Pad2)") (class "Default")
      (node (ref "R126") (pin "2") (pinfunction "2_2") (pintype "passive"))
      (node (ref "VT23") (pin "1") (pinfunction "1_1") (pintype "passive"))
    )
    (net (code "74") (name "Net-(R142-Pad2)") (class "Default")
      (node (ref "R142") (pin "2") (pinfunction "2_2") (pintype "passive"))
      (node (ref "VT24") (pin "1") (pinfunction "1_1") (pintype "passive"))
    )
    (net (code "75") (name "Net-(R143-Pad2)") (class "Default")
      (node (ref "R143") (pin "2") (pinfunction "2_2") (pintype "passive"))
      (node (ref "VT25") (pin "1") (pinfunction "1_1") (pintype "passive"))
    )
    (net (code "76") (name "Net-(R144-Pad2)") (class "Default")
      (node (ref "R144") (pin "2") (pinfunction "2_2") (pintype "passive"))
      (node (ref "VT26") (pin "1") (pinfunction "1_1") (pintype "passive"))
    )
    (net (code "77") (name "unconnected-(DA38-NC-Pad3)") (class "Default")
      (node (ref "DA38") (pin "3") (pinfunction "NC_3") (pintype "passive+no_connect"))
    )
    (net (code "78") (name "unconnected-(DA39-NC-Pad3)") (class "Default")
      (node (ref "DA39") (pin "3") (pinfunction "NC_3") (pintype "passive+no_connect"))
    )
    (net (code "79") (name "unconnected-(DA40-NC-Pad3)") (class "Default")
      (node (ref "DA40") (pin "3") (pinfunction "NC_3") (pintype "passive+no_connect"))
    )
    (net (code "80") (name "unconnected-(DA44-NC-Pad3)") (class "Default")
      (node (ref "DA44") (pin "3") (pinfunction "NC_3") (pintype "passive+no_connect"))
    )
    (net (code "81") (name "unconnected-(DA45-NC-Pad3)") (class "Default")
      (node (ref "DA45") (pin "3") (pinfunction "NC_3") (pintype "passive+no_connect"))
    )
    (net (code "82") (name "unconnected-(DA46-NC-Pad3)") (class "Default")
      (node (ref "DA46") (pin "3") (pinfunction "NC_3") (pintype "passive+no_connect"))
    )
    (net (code "83") (name "unconnected-(DA50-NC-Pad3)") (class "Default")
      (node (ref "DA50") (pin "3") (pinfunction "NC_3") (pintype "passive+no_connect"))
    )
    (net (code "84") (name "unconnected-(DA51-NC-Pad3)") (class "Default")
      (node (ref "DA51") (pin "3") (pinfunction "NC_3") (pintype "passive+no_connect"))
    )
    (net (code "85") (name "unconnected-(DA52-NC-Pad3)") (class "Default")
      (node (ref "DA52") (pin "3") (pinfunction "NC_3") (pintype "passive+no_connect"))
    )
  )
)
